# DAC.net
KiCad netlist of a schematic drawn in Altium Designer
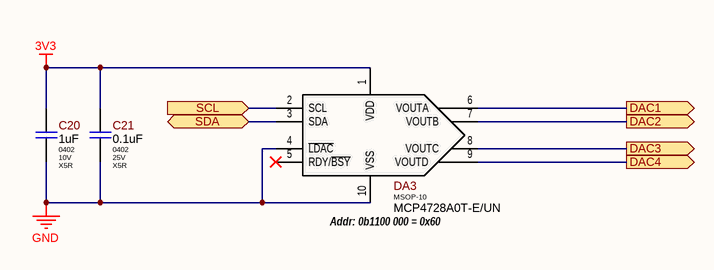
[diagram p0: DAC.SchDoc]

(export (version "E")
  (design (tool "Eeschema 10.0.6"))
  (components
    (comp (ref "C20")
      (value "1uF")
      (footprint "C_CERAMIC_0402_MED")
      (description "1uF 10V Х5R ±10% 0402 Ceramic Capacitor RoHS")
      (fields
        (field (name "PACKAGE") "0402")
        (field (name "VOLTAGE") "10V")
        (field (name "DIELECTRIC TYPE") "X5R")
        (field (name "PART NUMBER") "CL05A105KP5NNNC")
        (field (name "MANUFACTURER") "Samsung Electro-Mechanics")
      )
      (libsource (lib "AjaxLibrary") (part "Capacitor-NonPolar"))
    )
    (comp (ref "C21")
      (value "0.1uF")
      (footprint "C_CERAMIC_0402_MED")
      (description "100nF 25V X5R ±10% 0402 Ceramic Capacitor RoHS")
      (fields
        (field (name "PACKAGE") "0402")
        (field (name "VOLTAGE") "25V")
        (field (name "DIELECTRIC TYPE") "X5R")
        (field (name "PART NUMBER") "CL05A104KA5NNNC")
        (field (name "MANUFACTURER") "Samsung Electro-Mechanics")
      )
      (libsource (lib "AjaxLibrary") (part "Capacitor-NonPolar"))
    )
    (comp (ref "DA3")
      (value "MCP4728A0T-E/UN")
      (footprint "MSOP-10")
      (description "12-Bit, Quad Digital-to-Analog Converter with EEPROM Memory, MSOP-10")
      (fields
        (field (name "PACKAGE") "MSOP-10")
        (field (name "PART NUMBER") "MCP4728A0T-E/UN")
        (field (name "MANUFACTURER") "Microchip Technology")
      )
      (libsource (lib "AjaxLibrary") (part "MCP4728"))
    )
  )
  (nets
    (net (code "1") (name "/DAC1") (class "Default")
      (node (ref "DA3") (pin "6") (pinfunction "VOUTA_6") (pintype "passive"))
    )
    (net (code "2") (name "/DAC2") (class "Default")
      (node (ref "DA3") (pin "7") (pinfunction "VOUTB_7") (pintype "passive"))
    )
    (net (code "3") (name "/DAC3") (class "Default")
      (node (ref "DA3") (pin "8") (pinfunction "VOUTC_8") (pintype "passive"))
    )
    (net (code "4") (name "/DAC4") (class "Default")
      (node (ref "DA3") (pin "9") (pinfunction "VOUTD_9") (pintype "passive"))
    )
    (net (code "5") (name "/SCL") (class "Default")
      (node (ref "DA3") (pin "2") (pinfunction "SCL_2") (pintype "passive"))
    )
    (net (code "6") (name "/SDA") (class "Default")
      (node (ref "DA3") (pin "3") (pinfunction "SDA_3") (pintype "passive"))
    )
    (net (code "7") (name "3V3") (class "Default")
      (node (ref "C20") (pin "1") (pinfunction "1_1") (pintype "passive"))
      (node (ref "C21") (pin "1") (pinfunction "1_1") (pintype "passive"))
      (node (ref "DA3") (pin "1") (pinfunction "VDD_1") (pintype "passive"))
    )
    (net (code "8") (name "GND") (class "Default")
      (node (ref "C20") (pin "2") (pinfunction "2_2") (pintype "passive"))
      (node (ref "C21") (pin "2") (pinfunction "2_2") (pintype "passive"))
      (node (ref "DA3") (pin "10") (pinfunction "VSS_10") (pintype "passive"))
      (node (ref "DA3") (pin "4") (pinfunction "~{LDAC}_4") (pintype "passive"))
    )
    (net (code "9") (name "unconnected-(DA3-RDY{slash}~{BSY}-Pad5)") (class "Default")
      (node (ref "DA3") (pin "5") (pinfunction "RDY/~{BSY}_5") (pintype "passive+no_connect"))
    )
  )
)
